# Large_Connector.net
KiCad netlist of a schematic drawn in Altium Designer
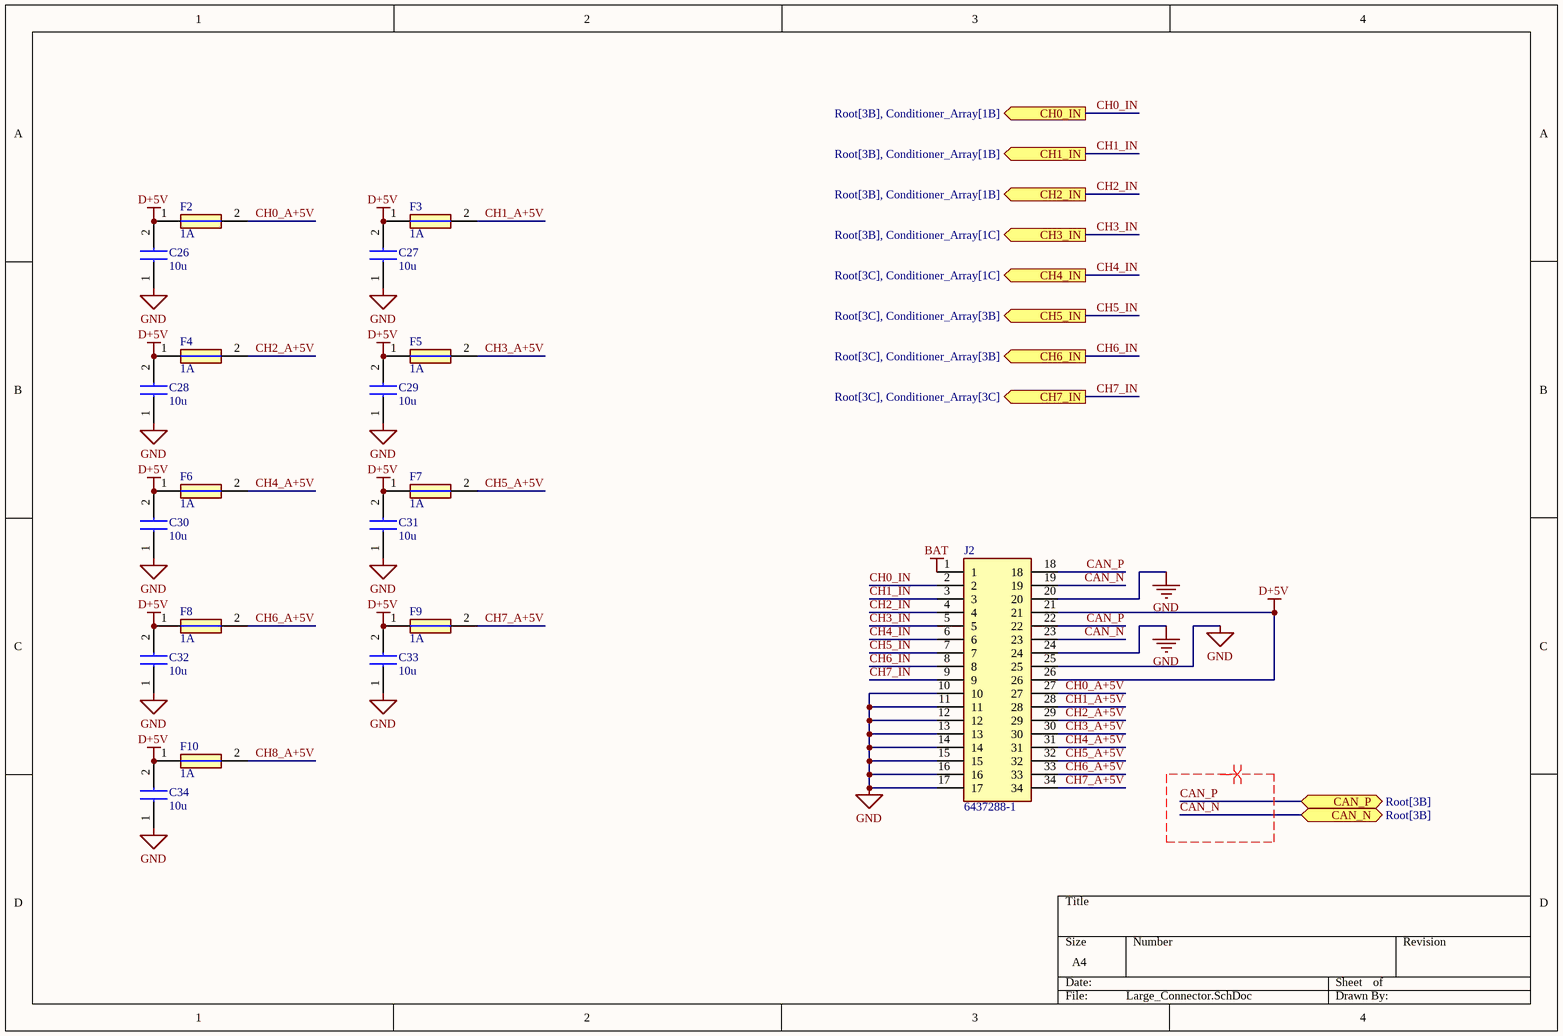
[diagram p0: Large_Connector.SchDoc]

(export (version "E")
  (design (tool "Eeschema 10.0.6"))
  (components
    (comp (ref "C26")
      (value "10u")
      (footprint "SamacSys:GRM18x")
      (description "GRM188R61A106ME69D")
      (fields (field (name "MOUSER PART NUMBER") "81-GRM188R61A106ME9D"))
      (libsource (lib "*") (part "GRM188R61A106ME69D"))
    )
    (comp (ref "C27")
      (value "10u")
      (footprint "SamacSys:GRM18x")
      (description "GRM188R61A106ME69D")
      (fields (field (name "MOUSER PART NUMBER") "81-GRM188R61A106ME9D"))
      (libsource (lib "*") (part "GRM188R61A106ME69D"))
    )
    (comp (ref "C28")
      (value "10u")
      (footprint "SamacSys:GRM18x")
      (description "GRM188R61A106ME69D")
      (fields (field (name "MOUSER PART NUMBER") "81-GRM188R61A106ME9D"))
      (libsource (lib "*") (part "GRM188R61A106ME69D"))
    )
    (comp (ref "C29")
      (value "10u")
      (footprint "SamacSys:GRM18x")
      (description "GRM188R61A106ME69D")
      (fields (field (name "MOUSER PART NUMBER") "81-GRM188R61A106ME9D"))
      (libsource (lib "*") (part "GRM188R61A106ME69D"))
    )
    (comp (ref "C30")
      (value "10u")
      (footprint "SamacSys:GRM18x")
      (description "GRM188R61A106ME69D")
      (fields (field (name "MOUSER PART NUMBER") "81-GRM188R61A106ME9D"))
      (libsource (lib "*") (part "GRM188R61A106ME69D"))
    )
    (comp (ref "C31")
      (value "10u")
      (footprint "SamacSys:GRM18x")
      (description "GRM188R61A106ME69D")
      (fields (field (name "MOUSER PART NUMBER") "81-GRM188R61A106ME9D"))
      (libsource (lib "*") (part "GRM188R61A106ME69D"))
    )
    (comp (ref "C32")
      (value "10u")
      (footprint "SamacSys:GRM18x")
      (description "GRM188R61A106ME69D")
      (fields (field (name "MOUSER PART NUMBER") "81-GRM188R61A106ME9D"))
      (libsource (lib "*") (part "GRM188R61A106ME69D"))
    )
    (comp (ref "C33")
      (value "10u")
      (footprint "SamacSys:GRM18x")
      (description "GRM188R61A106ME69D")
      (fields (field (name "MOUSER PART NUMBER") "81-GRM188R61A106ME9D"))
      (libsource (lib "*") (part "GRM188R61A106ME69D"))
    )
    (comp (ref "C34")
      (value "10u")
      (footprint "SamacSys:GRM18x")
      (description "GRM188R61A106ME69D")
      (fields (field (name "MOUSER PART NUMBER") "81-GRM188R61A106ME9D"))
      (libsource (lib "*") (part "GRM188R61A106ME69D"))
    )
    (comp (ref "F2")
      (value "1A")
      (footprint "SamacSys:ERBRE0R50V")
      (description "ERB-RE1R00V")
      (fields (field (name "MOUSER PART NUMBER") "667-ERB-RE1R00V"))
      (libsource (lib "SamacSys") (part "ERB-RE1R00V"))
    )
    (comp (ref "F3")
      (value "1A")
      (footprint "SamacSys:ERBRE0R50V")
      (description "ERB-RE1R00V")
      (fields (field (name "MOUSER PART NUMBER") "667-ERB-RE1R00V"))
      (libsource (lib "SamacSys") (part "ERB-RE1R00V"))
    )
    (comp (ref "F4")
      (value "1A")
      (footprint "SamacSys:ERBRE0R50V")
      (description "ERB-RE1R00V")
      (fields (field (name "MOUSER PART NUMBER") "667-ERB-RE1R00V"))
      (libsource (lib "SamacSys") (part "ERB-RE1R00V"))
    )
    (comp (ref "F5")
      (value "1A")
      (footprint "SamacSys:ERBRE0R50V")
      (description "ERB-RE1R00V")
      (fields (field (name "MOUSER PART NUMBER") "667-ERB-RE1R00V"))
      (libsource (lib "SamacSys") (part "ERB-RE1R00V"))
    )
    (comp (ref "F6")
      (value "1A")
      (footprint "SamacSys:ERBRE0R50V")
      (description "ERB-RE1R00V")
      (fields (field (name "MOUSER PART NUMBER") "667-ERB-RE1R00V"))
      (libsource (lib "SamacSys") (part "ERB-RE1R00V"))
    )
    (comp (ref "F7")
      (value "1A")
      (footprint "SamacSys:ERBRE0R50V")
      (description "ERB-RE1R00V")
      (fields (field (name "MOUSER PART NUMBER") "667-ERB-RE1R00V"))
      (libsource (lib "SamacSys") (part "ERB-RE1R00V"))
    )
    (comp (ref "F8")
      (value "1A")
      (footprint "SamacSys:ERBRE0R50V")
      (description "ERB-RE1R00V")
      (fields (field (name "MOUSER PART NUMBER") "667-ERB-RE1R00V"))
      (libsource (lib "SamacSys") (part "ERB-RE1R00V"))
    )
    (comp (ref "F9")
      (value "1A")
      (footprint "SamacSys:ERBRE0R50V")
      (description "ERB-RE1R00V")
      (fields (field (name "MOUSER PART NUMBER") "667-ERB-RE1R00V"))
      (libsource (lib "SamacSys") (part "ERB-RE1R00V"))
    )
    (comp (ref "F10")
      (value "1A")
      (footprint "SamacSys:ERBRE0R50V")
      (description "ERB-RE1R00V")
      (fields (field (name "MOUSER PART NUMBER") "667-ERB-RE1R00V"))
      (libsource (lib "SamacSys") (part "ERB-RE1R00V"))
    )
    (comp (ref "J2")
      (value "6437288-1")
      (footprint "SamacSys:6437288-1")
      (description "Connector")
      (fields (field (name "MOUSER PART NUMBER") "571-6437288-1"))
      (libsource (lib "SamacSys") (part "6437288-1"))
    )
  )
  (nets
    (net (code "1") (name "/CAN_N") (class "Default")
      (node (ref "J2") (pin "19") (pinfunction "19_19") (pintype "passive"))
      (node (ref "J2") (pin "23") (pinfunction "23_23") (pintype "passive"))
    )
    (net (code "2") (name "/CAN_P") (class "Default")
      (node (ref "J2") (pin "18") (pinfunction "18_18") (pintype "passive"))
      (node (ref "J2") (pin "22") (pinfunction "22_22") (pintype "passive"))
    )
    (net (code "3") (name "/CH0_A+5V") (class "Default")
      (node (ref "F2") (pin "2") (pinfunction "2_2") (pintype "passive"))
      (node (ref "J2") (pin "27") (pinfunction "27_27") (pintype "passive"))
    )
    (net (code "4") (name "/CH0_IN") (class "Default")
      (node (ref "J2") (pin "2") (pinfunction "2_2") (pintype "passive"))
    )
    (net (code "5") (name "/CH1_A+5V") (class "Default")
      (node (ref "F3") (pin "2") (pinfunction "2_2") (pintype "passive"))
      (node (ref "J2") (pin "28") (pinfunction "28_28") (pintype "passive"))
    )
    (net (code "6") (name "/CH1_IN") (class "Default")
      (node (ref "J2") (pin "3") (pinfunction "3_3") (pintype "passive"))
    )
    (net (code "7") (name "/CH2_A+5V") (class "Default")
      (node (ref "F4") (pin "2") (pinfunction "2_2") (pintype "passive"))
      (node (ref "J2") (pin "29") (pinfunction "29_29") (pintype "passive"))
    )
    (net (code "8") (name "/CH2_IN") (class "Default")
      (node (ref "J2") (pin "4") (pinfunction "4_4") (pintype "passive"))
    )
    (net (code "9") (name "/CH3_A+5V") (class "Default")
      (node (ref "F5") (pin "2") (pinfunction "2_2") (pintype "passive"))
      (node (ref "J2") (pin "30") (pinfunction "30_30") (pintype "passive"))
    )
    (net (code "10") (name "/CH3_IN") (class "Default")
      (node (ref "J2") (pin "5") (pinfunction "5_5") (pintype "passive"))
    )
    (net (code "11") (name "/CH4_A+5V") (class "Default")
      (node (ref "F6") (pin "2") (pinfunction "2_2") (pintype "passive"))
      (node (ref "J2") (pin "31") (pinfunction "31_31") (pintype "passive"))
    )
    (net (code "12") (name "/CH4_IN") (class "Default")
      (node (ref "J2") (pin "6") (pinfunction "6_6") (pintype "passive"))
    )
    (net (code "13") (name "/CH5_A+5V") (class "Default")
      (node (ref "F7") (pin "2") (pinfunction "2_2") (pintype "passive"))
      (node (ref "J2") (pin "32") (pinfunction "32_32") (pintype "passive"))
    )
    (net (code "14") (name "/CH5_IN") (class "Default")
      (node (ref "J2") (pin "7") (pinfunction "7_7") (pintype "passive"))
    )
    (net (code "15") (name "/CH6_A+5V") (class "Default")
      (node (ref "F8") (pin "2") (pinfunction "2_2") (pintype "passive"))
      (node (ref "J2") (pin "33") (pinfunction "33_33") (pintype "passive"))
    )
    (net (code "16") (name "/CH6_IN") (class "Default")
      (node (ref "J2") (pin "8") (pinfunction "8_8") (pintype "passive"))
    )
    (net (code "17") (name "/CH7_A+5V") (class "Default")
      (node (ref "F9") (pin "2") (pinfunction "2_2") (pintype "passive"))
      (node (ref "J2") (pin "34") (pinfunction "34_34") (pintype "passive"))
    )
    (net (code "18") (name "/CH7_IN") (class "Default")
      (node (ref "J2") (pin "9") (pinfunction "9_9") (pintype "passive"))
    )
    (net (code "19") (name "/CH8_A+5V") (class "Default")
      (node (ref "F10") (pin "2") (pinfunction "2_2") (pintype "passive"))
    )
    (net (code "20") (name "BAT") (class "Default")
      (node (ref "J2") (pin "1") (pinfunction "1_1") (pintype "passive"))
    )
    (net (code "21") (name "D+5V") (class "Default")
      (node (ref "C26") (pin "2") (pinfunction "2_2") (pintype "passive"))
      (node (ref "C27") (pin "2") (pinfunction "2_2") (pintype "passive"))
      (node (ref "C28") (pin "2") (pinfunction "2_2") (pintype "passive"))
      (node (ref "C29") (pin "2") (pinfunction "2_2") (pintype "passive"))
      (node (ref "C30") (pin "2") (pinfunction "2_2") (pintype "passive"))
      (node (ref "C31") (pin "2") (pinfunction "2_2") (pintype "passive"))
      (node (ref "C32") (pin "2") (pinfunction "2_2") (pintype "passive"))
      (node (ref "C33") (pin "2") (pinfunction "2_2") (pintype "passive"))
      (node (ref "C34") (pin "2") (pinfunction "2_2") (pintype "passive"))
      (node (ref "F10") (pin "1") (pinfunction "1_1") (pintype "passive"))
      (node (ref "F2") (pin "1") (pinfunction "1_1") (pintype "passive"))
      (node (ref "F3") (pin "1") (pinfunction "1_1") (pintype "passive"))
      (node (ref "F4") (pin "1") (pinfunction "1_1") (pintype "passive"))
      (node (ref "F5") (pin "1") (pinfunction "1_1") (pintype "passive"))
      (node (ref "F6") (pin "1") (pinfunction "1_1") (pintype "passive"))
      (node (ref "F7") (pin "1") (pinfunction "1_1") (pintype "passive"))
      (node (ref "F8") (pin "1") (pinfunction "1_1") (pintype "passive"))
      (node (ref "F9") (pin "1") (pinfunction "1_1") (pintype "passive"))
      (node (ref "J2") (pin "21") (pinfunction "21_21") (pintype "passive"))
      (node (ref "J2") (pin "26") (pinfunction "26_26") (pintype "passive"))
    )
    (net (code "22") (name "GND") (class "Default")
      (node (ref "C26") (pin "1") (pinfunction "1_1") (pintype "passive"))
      (node (ref "C27") (pin "1") (pinfunction "1_1") (pintype "passive"))
      (node (ref "C28") (pin "1") (pinfunction "1_1") (pintype "passive"))
      (node (ref "C29") (pin "1") (pinfunction "1_1") (pintype "passive"))
      (node (ref "C30") (pin "1") (pinfunction "1_1") (pintype "passive"))
      (node (ref "C31") (pin "1") (pinfunction "1_1") (pintype "passive"))
      (node (ref "C32") (pin "1") (pinfunction "1_1") (pintype "passive"))
      (node (ref "C33") (pin "1") (pinfunction "1_1") (pintype "passive"))
      (node (ref "C34") (pin "1") (pinfunction "1_1") (pintype "passive"))
      (node (ref "J2") (pin "10") (pinfunction "10_10") (pintype "passive"))
      (node (ref "J2") (pin "11") (pinfunction "11_11") (pintype "passive"))
      (node (ref "J2") (pin "12") (pinfunction "12_12") (pintype "passive"))
      (node (ref "J2") (pin "13") (pinfunction "13_13") (pintype "passive"))
      (node (ref "J2") (pin "14") (pinfunction "14_14") (pintype "passive"))
      (node (ref "J2") (pin "15") (pinfunction "15_15") (pintype "passive"))
      (node (ref "J2") (pin "16") (pinfunction "16_16") (pintype "passive"))
      (node (ref "J2") (pin "17") (pinfunction "17_17") (pintype "passive"))
      (node (ref "J2") (pin "20") (pinfunction "20_20") (pintype "passive"))
      (node (ref "J2") (pin "24") (pinfunction "24_24") (pintype "passive"))
      (node (ref "J2") (pin "25") (pinfunction "25_25") (pintype "passive"))
    )
  )
)
